# esp32_part_20190819.net
KiCad netlist of a schematic drawn in EAGLE
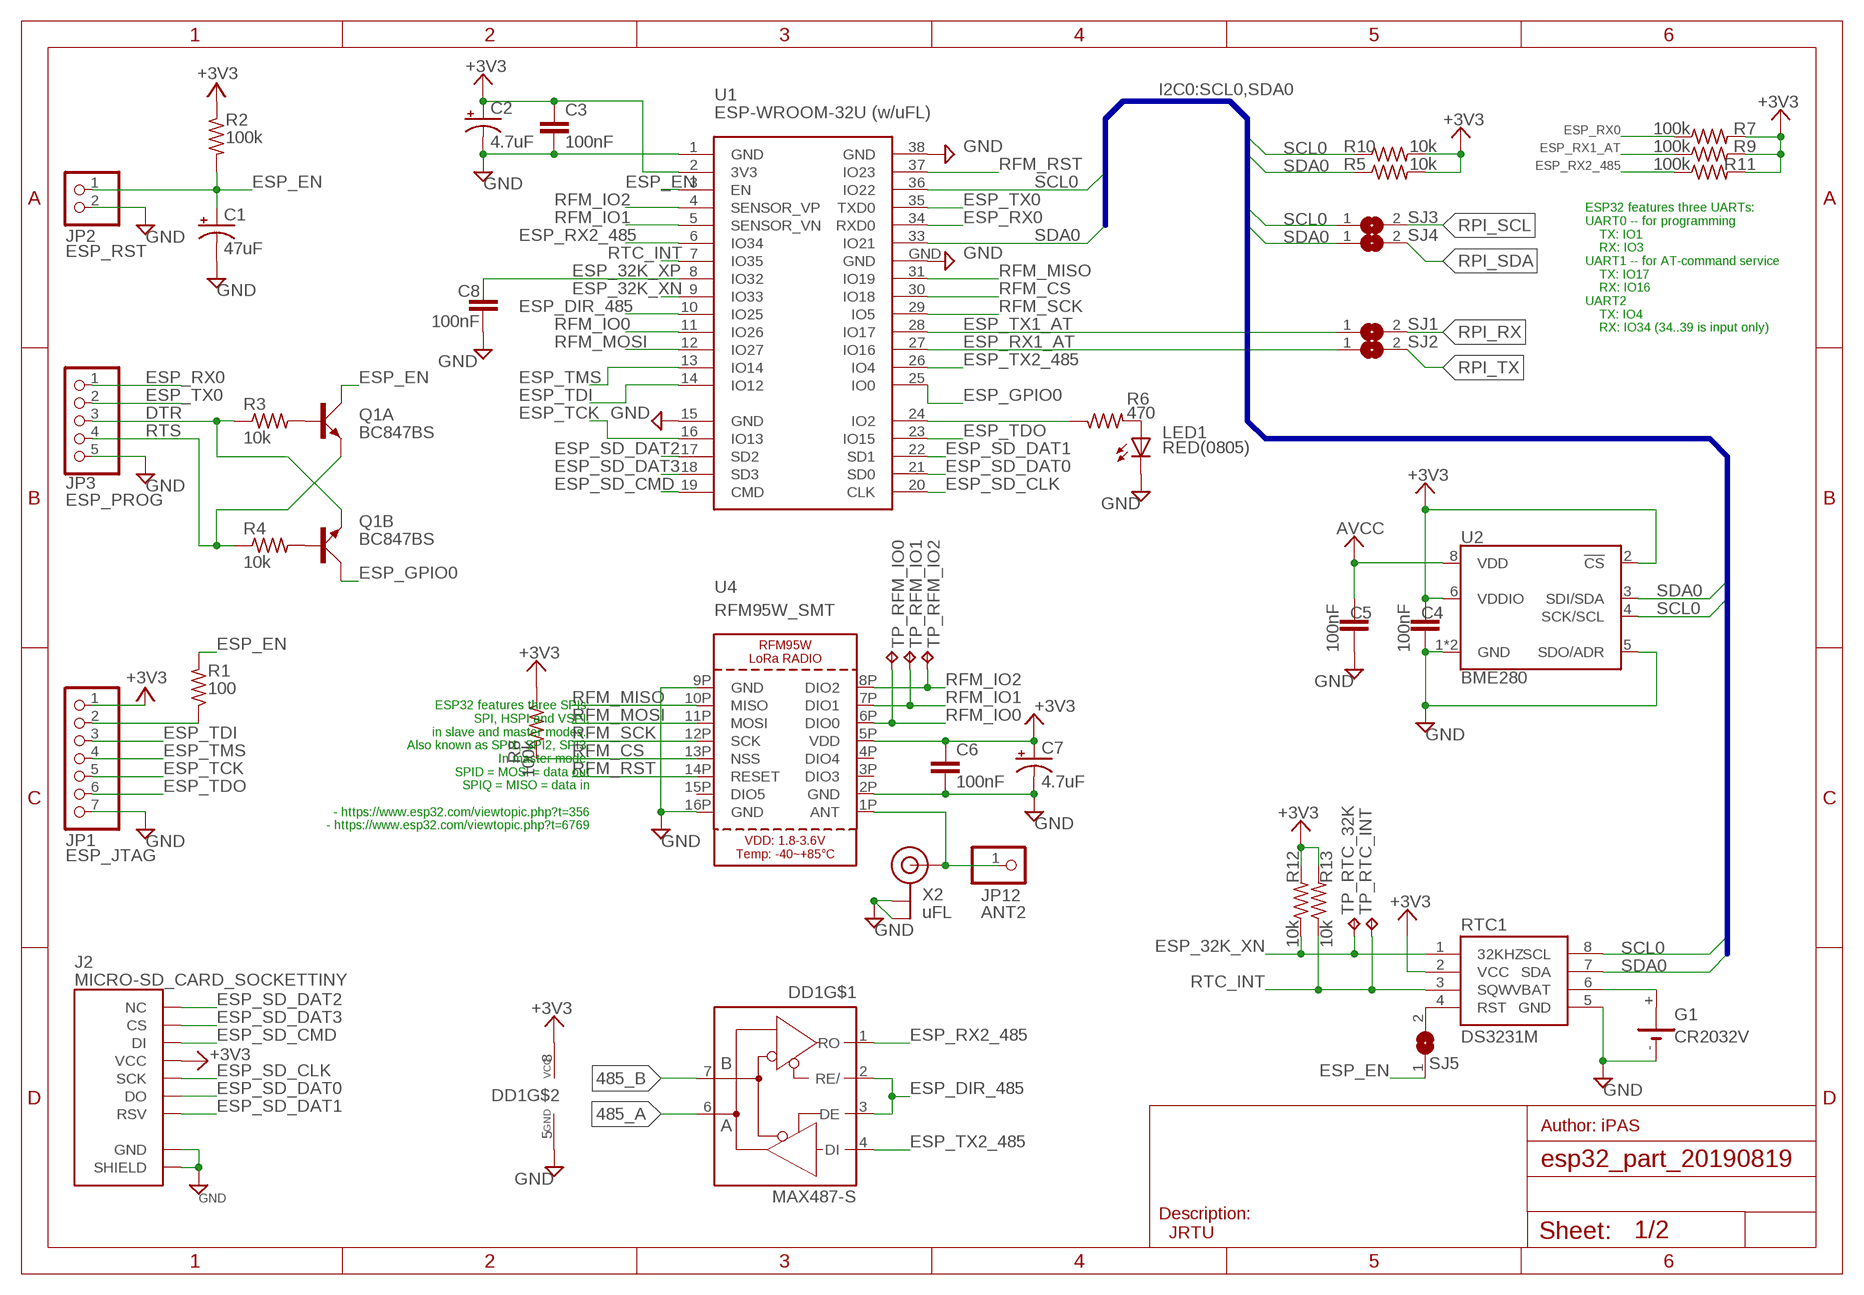
[diagram p0: schematic, sheet 1]
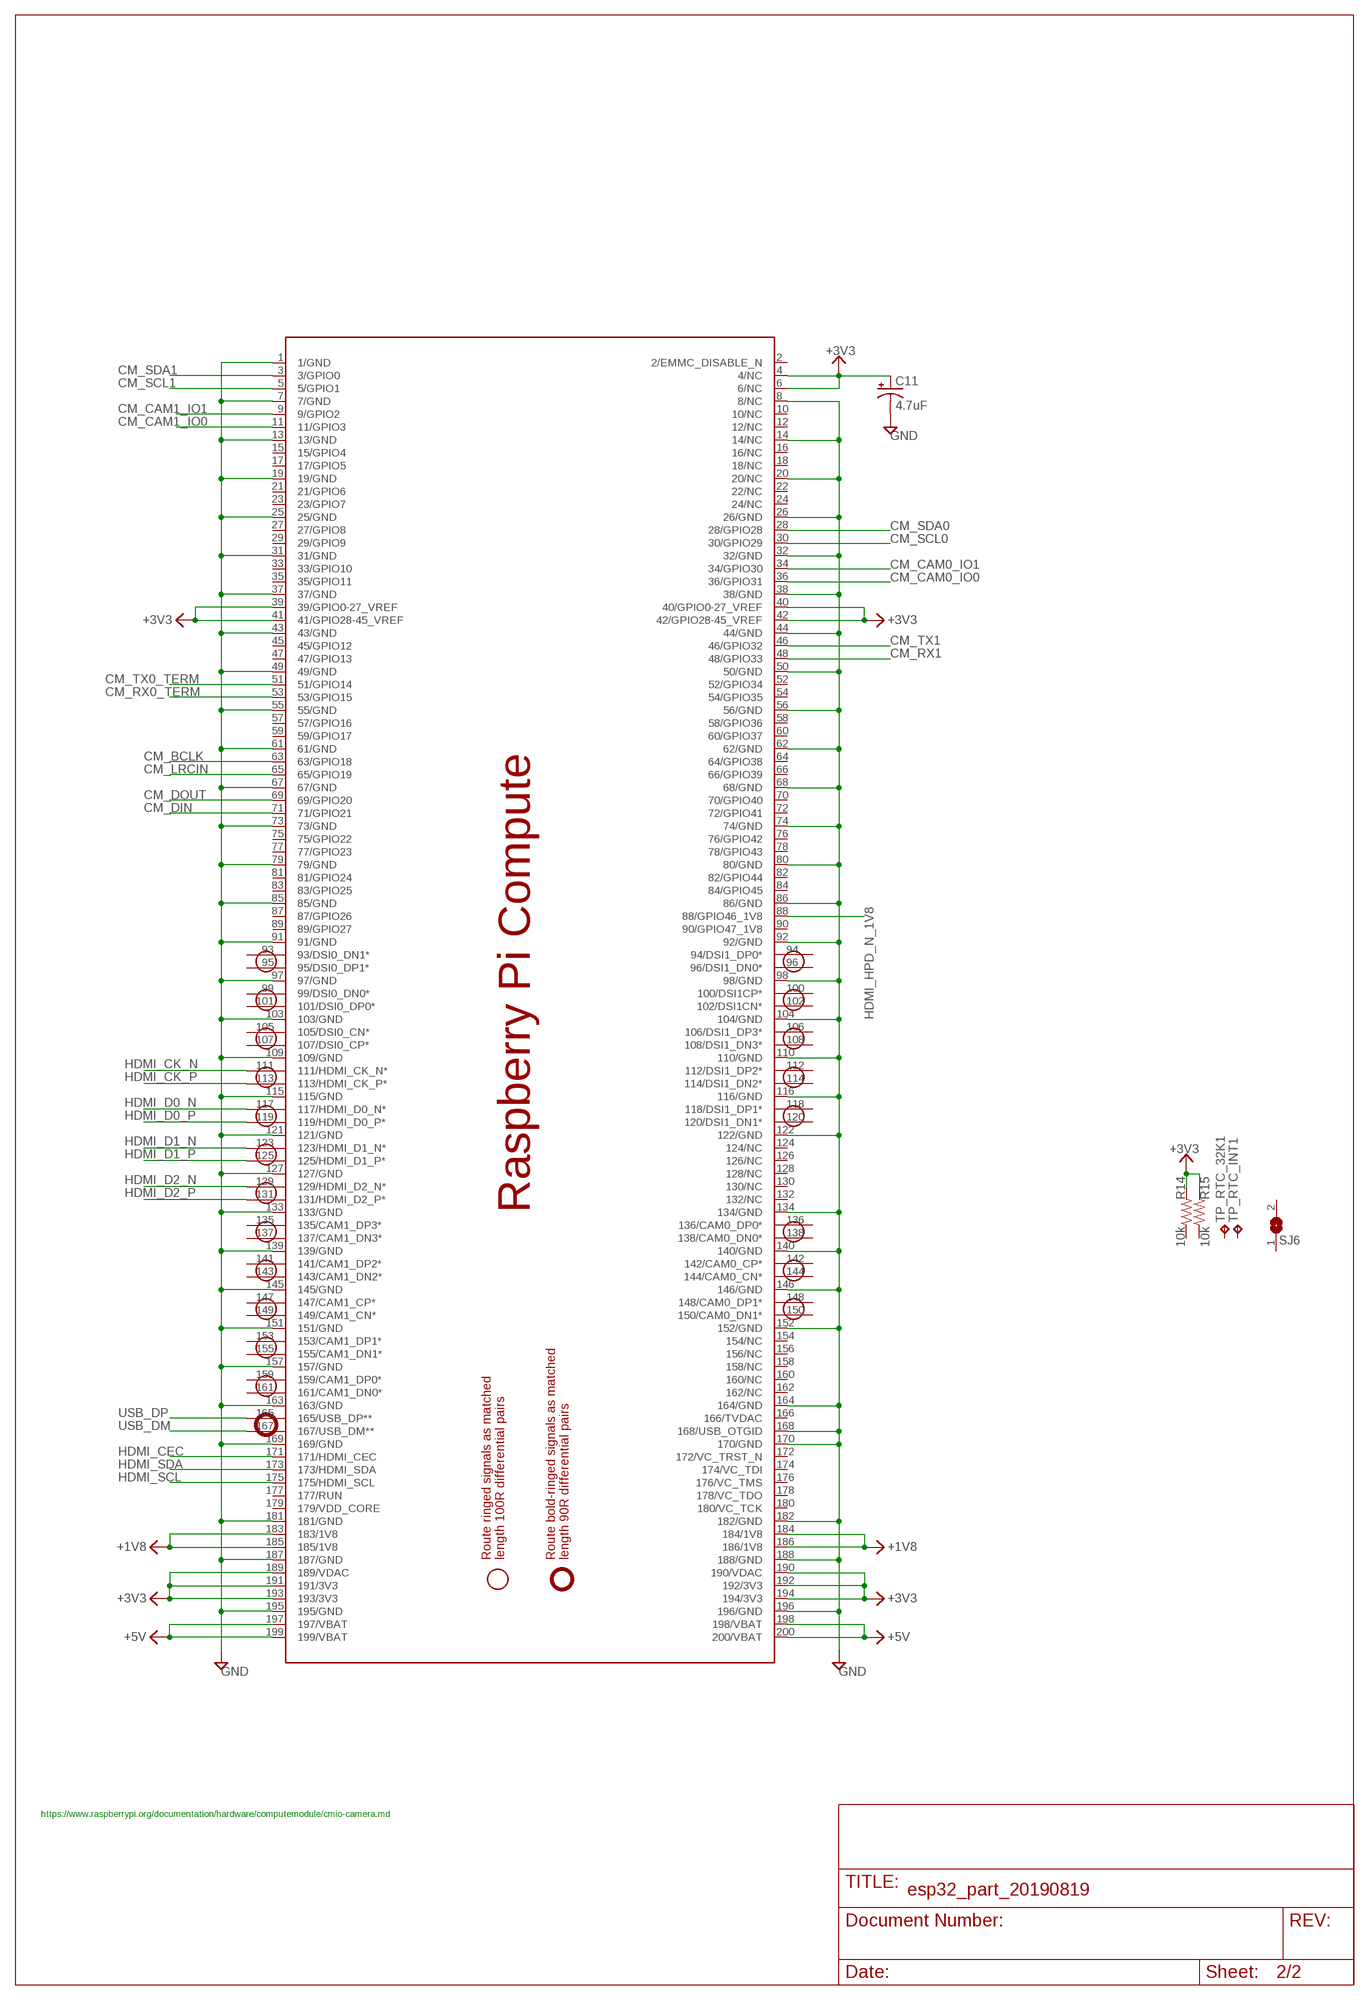
[diagram p1: schematic, sheet 2]

(export (version "E")
  (design (tool "Eeschema 10.0.6"))
  (components
    (comp (ref "C11")
      (value "4.7uF")
      (footprint "eagle-import:RCL_150CLZ-1014")
      (libsource (lib "eagle-import") (part "RCL_CPOL-US150CLZ-1014"))
    )
    (comp (ref "R14")
      (value "10k")
      (footprint "eagle-import:RCL_M0805")
      (libsource (lib "eagle-import") (part "RCL_R-USM0805"))
    )
    (comp (ref "R15")
      (value "10k")
      (footprint "eagle-import:RCL_M0805")
      (libsource (lib "eagle-import") (part "RCL_R-USM0805"))
    )
    (comp (ref "SJ6")
      (value "SOLDERJUMPERREFLOW")
      (footprint "eagle-import:SOLDERJUMPER_REFLOW")
      (libsource (lib "eagle-import") (part "SOLDERJUMPERREFLOW"))
    )
    (comp (ref "SODIMM")
      (value "RPI_COMPUTE")
      (footprint "eagle-import:RPI_COMPUTE")
      (libsource (lib "eagle-import") (part "RPI_COMPUTE"))
    )
    (comp (ref "TP_RTC_32K1")
      (value "TPB1,27")
      (footprint "eagle-import:B1,27")
      (libsource (lib "eagle-import") (part "TPB1,27"))
    )
    (comp (ref "TP_RTC_INT1")
      (value "TPB1,27")
      (footprint "eagle-import:B1,27")
      (libsource (lib "eagle-import") (part "TPB1,27"))
    )
    (comp (ref "C1")
      (value "47uF")
      (footprint "eagle-import:RCL_150CLZ-1014")
      (libsource (lib "eagle-import") (part "RCL_CPOL-US150CLZ-1014"))
    )
    (comp (ref "C2")
      (value "4.7uF")
      (footprint "eagle-import:RCL_150CLZ-1014")
      (libsource (lib "eagle-import") (part "RCL_CPOL-US150CLZ-1014"))
    )
    (comp (ref "C3")
      (value "100nF")
      (footprint "eagle-import:RCL_C1206")
      (libsource (lib "eagle-import") (part "RCL_C-EUC1206"))
    )
    (comp (ref "C4")
      (value "100nF")
      (footprint "eagle-import:RCL_C1206")
      (libsource (lib "eagle-import") (part "RCL_C-EUC1206"))
    )
    (comp (ref "C5")
      (value "100nF")
      (footprint "eagle-import:RCL_C1206")
      (libsource (lib "eagle-import") (part "RCL_C-EUC1206"))
    )
    (comp (ref "C6")
      (value "100nF")
      (footprint "eagle-import:RCL_C1206")
      (libsource (lib "eagle-import") (part "RCL_C-EUC1206"))
    )
    (comp (ref "C7")
      (value "4.7uF")
      (footprint "eagle-import:RCL_150CLZ-1014")
      (libsource (lib "eagle-import") (part "RCL_CPOL-US150CLZ-1014"))
    )
    (comp (ref "C8")
      (value "100nF")
      (footprint "eagle-import:RCL_C1206")
      (libsource (lib "eagle-import") (part "RCL_C-EUC1206"))
    )
    (comp (ref "DD1")
      (value "MAX487-S")
      (footprint "eagle-import:SO08")
      (libsource (lib "eagle-import") (part "MAX487-S"))
    )
    (comp (ref "G1")
      (value "CR2032V")
      (footprint "eagle-import:CR2032V")
      (libsource (lib "eagle-import") (part "CR2032V"))
    )
    (comp (ref "J2")
      (value "MICRO-SD_CARD_SOCKETTINY")
      (footprint "eagle-import:MICROSD_TINY")
      (libsource (lib "eagle-import") (part "MICRO-SD_CARD_SOCKETTINY"))
    )
    (comp (ref "JP1")
      (value "ESP_JTAG")
      (footprint "eagle-import:1X07")
      (libsource (lib "eagle-import") (part "PINHD-1X7"))
    )
    (comp (ref "JP2")
      (value "ESP_RST")
      (footprint "eagle-import:1X02")
      (libsource (lib "eagle-import") (part "PINHD-1X2"))
    )
    (comp (ref "JP3")
      (value "ESP_PROG")
      (footprint "eagle-import:1X05")
      (libsource (lib "eagle-import") (part "PINHD-1X5"))
    )
    (comp (ref "JP12")
      (value "ANT2")
      (footprint "eagle-import:1X01_ROUND")
      (libsource (lib "eagle-import") (part "HEADER-1X1ROUND"))
    )
    (comp (ref "LED1")
      (value "RED(0805)")
      (footprint "eagle-import:CHIP-LED0805")
      (libsource (lib "eagle-import") (part "LEDCHIP-LED0805"))
    )
    (comp (ref "Q1")
      (value "BC847BS")
      (footprint "eagle-import:SOT363_PHILIPS")
      (libsource (lib "eagle-import") (part "BC847BS"))
    )
    (comp (ref "R1")
      (value "100")
      (footprint "eagle-import:RCL_M0805")
      (libsource (lib "eagle-import") (part "RCL_R-USM0805"))
    )
    (comp (ref "R2")
      (value "100k")
      (footprint "eagle-import:RCL_M0805")
      (libsource (lib "eagle-import") (part "RCL_R-USM0805"))
    )
    (comp (ref "R3")
      (value "10k")
      (footprint "eagle-import:RCL_M0805")
      (libsource (lib "eagle-import") (part "RCL_R-USM0805"))
    )
    (comp (ref "R4")
      (value "10k")
      (footprint "eagle-import:RCL_M0805")
      (libsource (lib "eagle-import") (part "RCL_R-USM0805"))
    )
    (comp (ref "R5")
      (value "10k")
      (footprint "eagle-import:RCL_M0805")
      (libsource (lib "eagle-import") (part "RCL_R-USM0805"))
    )
    (comp (ref "R6")
      (value "470")
      (footprint "eagle-import:RCL_M0805")
      (libsource (lib "eagle-import") (part "RCL_R-USM0805"))
    )
    (comp (ref "R7")
      (value "100k")
      (footprint "eagle-import:RCL_M0805")
      (libsource (lib "eagle-import") (part "RCL_R-USM0805"))
    )
    (comp (ref "R8")
      (value "100k")
      (footprint "eagle-import:RCL_M0805")
      (libsource (lib "eagle-import") (part "RCL_R-USM0805"))
    )
    (comp (ref "R9")
      (value "100k")
      (footprint "eagle-import:RCL_M0805")
      (libsource (lib "eagle-import") (part "RCL_R-USM0805"))
    )
    (comp (ref "R10")
      (value "10k")
      (footprint "eagle-import:RCL_M0805")
      (libsource (lib "eagle-import") (part "RCL_R-USM0805"))
    )
    (comp (ref "R11")
      (value "100k")
      (footprint "eagle-import:RCL_M0805")
      (libsource (lib "eagle-import") (part "RCL_R-USM0805"))
    )
    (comp (ref "R12")
      (value "10k")
      (footprint "eagle-import:RCL_M0805")
      (libsource (lib "eagle-import") (part "RCL_R-USM0805"))
    )
    (comp (ref "R13")
      (value "10k")
      (footprint "eagle-import:RCL_M0805")
      (libsource (lib "eagle-import") (part "RCL_R-USM0805"))
    )
    (comp (ref "RTC1")
      (value "DS3231M")
      (footprint "eagle-import:SO08")
      (libsource (lib "eagle-import") (part "DS3231M"))
    )
    (comp (ref "SJ1")
      (value "SOLDERJUMPERREFLOW")
      (footprint "eagle-import:SOLDERJUMPER_REFLOW")
      (libsource (lib "eagle-import") (part "SOLDERJUMPERREFLOW"))
    )
    (comp (ref "SJ2")
      (value "SOLDERJUMPERREFLOW")
      (footprint "eagle-import:SOLDERJUMPER_REFLOW")
      (libsource (lib "eagle-import") (part "SOLDERJUMPERREFLOW"))
    )
    (comp (ref "SJ3")
      (value "SOLDERJUMPERREFLOW")
      (footprint "eagle-import:SOLDERJUMPER_REFLOW")
      (libsource (lib "eagle-import") (part "SOLDERJUMPERREFLOW"))
    )
    (comp (ref "SJ4")
      (value "SOLDERJUMPERREFLOW")
      (footprint "eagle-import:SOLDERJUMPER_REFLOW")
      (libsource (lib "eagle-import") (part "SOLDERJUMPERREFLOW"))
    )
    (comp (ref "SJ5")
      (value "SOLDERJUMPERREFLOW")
      (footprint "eagle-import:SOLDERJUMPER_REFLOW")
      (libsource (lib "eagle-import") (part "SOLDERJUMPERREFLOW"))
    )
    (comp (ref "TP_RFM_IO0")
      (value "TPB1,27")
      (footprint "eagle-import:B1,27")
      (libsource (lib "eagle-import") (part "TPB1,27"))
    )
    (comp (ref "TP_RFM_IO1")
      (value "TPB1,27")
      (footprint "eagle-import:B1,27")
      (libsource (lib "eagle-import") (part "TPB1,27"))
    )
    (comp (ref "TP_RFM_IO2")
      (value "TPB1,27")
      (footprint "eagle-import:B1,27")
      (libsource (lib "eagle-import") (part "TPB1,27"))
    )
    (comp (ref "TP_RTC_32K")
      (value "TPB1,27")
      (footprint "eagle-import:B1,27")
      (libsource (lib "eagle-import") (part "TPB1,27"))
    )
    (comp (ref "TP_RTC_INT")
      (value "TPB1,27")
      (footprint "eagle-import:B1,27")
      (libsource (lib "eagle-import") (part "TPB1,27"))
    )
    (comp (ref "U1")
      (value "ESP-WROOM-32U (w/uFL)")
      (footprint "eagle-import:ESP-WROOM-32")
      (libsource (lib "eagle-import") (part "ESP-WROOM-32"))
    )
    (comp (ref "U2")
      (value "BME280")
      (footprint "eagle-import:LGA-8-2.5X2.5")
      (libsource (lib "eagle-import") (part "BME280"))
    )
    (comp (ref "U4")
      (value "RFM95W_SMT")
      (footprint "eagle-import:RFMHCW_SMT")
      (libsource (lib "eagle-import") (part "RFM95W_SMT"))
    )
    (comp (ref "X2")
      (value "uFL")
      (footprint "eagle-import:U.FL")
      (libsource (lib "eagle-import") (part "ANTENNA_U.FL"))
    )
  )
  (nets
    (net (code "2") (name "+3V3") (class "Default")
      (node (ref "C11") (pin "+") (pinfunction "+_+") (pintype "passive"))
      (node (ref "C2") (pin "+") (pinfunction "+_+") (pintype "passive"))
      (node (ref "C3") (pin "1") (pinfunction "1_1") (pintype "passive"))
      (node (ref "C4") (pin "1") (pinfunction "1_1") (pintype "passive"))
      (node (ref "C6") (pin "1") (pinfunction "1_1") (pintype "passive"))
      (node (ref "C7") (pin "+") (pinfunction "+_+") (pintype "passive"))
      (node (ref "DD1") (pin "8") (pinfunction "VCC_8") (pintype "power_in"))
      (node (ref "J2") (pin "4") (pinfunction "VCC_4") (pintype "bidirectional"))
      (node (ref "JP1") (pin "1") (pinfunction "1_1") (pintype "passive"))
      (node (ref "R10") (pin "2") (pinfunction "2_2") (pintype "passive"))
      (node (ref "R11") (pin "2") (pinfunction "2_2") (pintype "passive"))
      (node (ref "R12") (pin "2") (pinfunction "2_2") (pintype "passive"))
      (node (ref "R13") (pin "2") (pinfunction "2_2") (pintype "passive"))
      (node (ref "R14") (pin "2") (pinfunction "2_2") (pintype "passive"))
      (node (ref "R15") (pin "2") (pinfunction "2_2") (pintype "passive"))
      (node (ref "R2") (pin "1") (pinfunction "1_1") (pintype "passive"))
      (node (ref "R5") (pin "2") (pinfunction "2_2") (pintype "passive"))
      (node (ref "R7") (pin "2") (pinfunction "2_2") (pintype "passive"))
      (node (ref "R8") (pin "1") (pinfunction "1_1") (pintype "passive"))
      (node (ref "R9") (pin "2") (pinfunction "2_2") (pintype "passive"))
      (node (ref "RTC1") (pin "2") (pinfunction "VCC_2") (pintype "power_in"))
      (node (ref "SODIMM") (pin "183") (pinfunction "183/1V8_183") (pintype "bidirectional"))
      (node (ref "SODIMM") (pin "184") (pinfunction "184/1V8_184") (pintype "bidirectional"))
      (node (ref "SODIMM") (pin "185") (pinfunction "185/1V8_185") (pintype "bidirectional"))
      (node (ref "SODIMM") (pin "186") (pinfunction "186/1V8_186") (pintype "bidirectional"))
      (node (ref "SODIMM") (pin "189") (pinfunction "189/VDAC_189") (pintype "bidirectional"))
      (node (ref "SODIMM") (pin "190") (pinfunction "190/VDAC_190") (pintype "bidirectional"))
      (node (ref "SODIMM") (pin "191") (pinfunction "191/3V3_191") (pintype "bidirectional"))
      (node (ref "SODIMM") (pin "192") (pinfunction "192/3V3_192") (pintype "bidirectional"))
      (node (ref "SODIMM") (pin "193") (pinfunction "193/3V3_193") (pintype "bidirectional"))
      (node (ref "SODIMM") (pin "194") (pinfunction "194/3V3_194") (pintype "bidirectional"))
      (node (ref "SODIMM") (pin "39") (pinfunction "39/GPIO0-27_VREF_39") (pintype "bidirectional"))
      (node (ref "SODIMM") (pin "4") (pinfunction "4/NC_4") (pintype "bidirectional"))
      (node (ref "SODIMM") (pin "40") (pinfunction "40/GPIO0-27_VREF_40") (pintype "bidirectional"))
      (node (ref "SODIMM") (pin "41") (pinfunction "41/GPIO28-45_VREF_41") (pintype "bidirectional"))
      (node (ref "SODIMM") (pin "42") (pinfunction "42/GPIO28-45_VREF_42") (pintype "bidirectional"))
      (node (ref "SODIMM") (pin "6") (pinfunction "6/NC_6") (pintype "bidirectional"))
      (node (ref "U1") (pin "2") (pinfunction "3V3_2") (pintype "power_in"))
      (node (ref "U2") (pin "2") (pinfunction "~{CS}_2") (pintype "bidirectional"))
      (node (ref "U2") (pin "6") (pinfunction "VDDIO_6") (pintype "bidirectional"))
      (node (ref "U4") (pin "5P") (pinfunction "VDD_5P") (pintype "power_in"))
    )
    (net (code "3") (name "+5V") (class "Default")
      (node (ref "SODIMM") (pin "197") (pinfunction "197/VBAT_197") (pintype "bidirectional"))
      (node (ref "SODIMM") (pin "198") (pinfunction "198/VBAT_198") (pintype "bidirectional"))
      (node (ref "SODIMM") (pin "199") (pinfunction "199/VBAT_199") (pintype "bidirectional"))
      (node (ref "SODIMM") (pin "200") (pinfunction "200/VBAT_200") (pintype "bidirectional"))
    )
    (net (code "5") (name "485_A") (class "Default")
      (node (ref "DD1") (pin "6") (pinfunction "A_6") (pintype "passive"))
    )
    (net (code "6") (name "485_B") (class "Default")
      (node (ref "DD1") (pin "7") (pinfunction "B_7") (pintype "passive"))
    )
    (net (code "7") (name "AVCC") (class "Default")
      (node (ref "C5") (pin "1") (pinfunction "1_1") (pintype "passive"))
      (node (ref "U2") (pin "8") (pinfunction "VDD_8") (pintype "bidirectional"))
    )
    (net (code "8") (name "CM_BCLK") (class "Default")
      (node (ref "SODIMM") (pin "63") (pinfunction "63/GPIO18_63") (pintype "bidirectional"))
    )
    (net (code "9") (name "CM_CAM0_IO0") (class "Default")
      (node (ref "SODIMM") (pin "36") (pinfunction "36/GPIO31_36") (pintype "bidirectional"))
    )
    (net (code "10") (name "CM_CAM0_IO1") (class "Default")
      (node (ref "SODIMM") (pin "34") (pinfunction "34/GPIO30_34") (pintype "bidirectional"))
    )
    (net (code "11") (name "CM_CAM1_IO0") (class "Default")
      (node (ref "SODIMM") (pin "11") (pinfunction "11/GPIO3_11") (pintype "bidirectional"))
    )
    (net (code "12") (name "CM_CAM1_IO1") (class "Default")
      (node (ref "SODIMM") (pin "9") (pinfunction "9/GPIO2_9") (pintype "bidirectional"))
    )
    (net (code "13") (name "CM_DIN") (class "Default")
      (node (ref "SODIMM") (pin "71") (pinfunction "71/GPIO21_71") (pintype "bidirectional"))
    )
    (net (code "14") (name "CM_DOUT") (class "Default")
      (node (ref "SODIMM") (pin "69") (pinfunction "69/GPIO20_69") (pintype "bidirectional"))
    )
    (net (code "15") (name "CM_LRCIN") (class "Default")
      (node (ref "SODIMM") (pin "65") (pinfunction "65/GPIO19_65") (pintype "bidirectional"))
    )
    (net (code "16") (name "CM_RX0_TERM") (class "Default")
      (node (ref "SODIMM") (pin "53") (pinfunction "53/GPIO15_53") (pintype "bidirectional"))
    )
    (net (code "17") (name "CM_RX1") (class "Default")
      (node (ref "SODIMM") (pin "48") (pinfunction "48/GPIO33_48") (pintype "bidirectional"))
    )
    (net (code "18") (name "CM_SCL0") (class "Default")
      (node (ref "SODIMM") (pin "30") (pinfunction "30/GPIO29_30") (pintype "bidirectional"))
    )
    (net (code "19") (name "CM_SCL1") (class "Default")
      (node (ref "SODIMM") (pin "5") (pinfunction "5/GPIO1_5") (pintype "bidirectional"))
    )
    (net (code "20") (name "CM_SDA0") (class "Default")
      (node (ref "SODIMM") (pin "28") (pinfunction "28/GPIO28_28") (pintype "bidirectional"))
    )
    (net (code "21") (name "CM_SDA1") (class "Default")
      (node (ref "SODIMM") (pin "3") (pinfunction "3/GPIO0_3") (pintype "bidirectional"))
    )
    (net (code "22") (name "CM_TX0_TERM") (class "Default")
      (node (ref "SODIMM") (pin "51") (pinfunction "51/GPIO14_51") (pintype "bidirectional"))
    )
    (net (code "23") (name "CM_TX1") (class "Default")
      (node (ref "SODIMM") (pin "46") (pinfunction "46/GPIO32_46") (pintype "bidirectional"))
    )
    (net (code "24") (name "DTR") (class "Default")
      (node (ref "JP3") (pin "3") (pinfunction "3_3") (pintype "passive"))
      (node (ref "Q1") (pin "4") (pinfunction "E_4") (pintype "passive"))
      (node (ref "R3") (pin "1") (pinfunction "1_1") (pintype "passive"))
    )
    (net (code "25") (name "ESP_32K_XN") (class "Default")
      (node (ref "R12") (pin "1") (pinfunction "1_1") (pintype "passive"))
      (node (ref "RTC1") (pin "1") (pinfunction "32KHZ_1") (pintype "output"))
      (node (ref "TP_RTC_32K") (pin "TP") (pinfunction "TP_TP") (pintype "input"))
      (node (ref "U1") (pin "9") (pinfunction "IO33_9") (pintype "bidirectional"))
    )
    (net (code "26") (name "ESP_32K_XP") (class "Default")
      (node (ref "C8") (pin "2") (pinfunction "2_2") (pintype "passive"))
      (node (ref "U1") (pin "8") (pinfunction "IO32_8") (pintype "bidirectional"))
    )
    (net (code "27") (name "ESP_DIR_485") (class "Default")
      (node (ref "DD1") (pin "2") (pinfunction "RE/_2") (pintype "input"))
      (node (ref "DD1") (pin "3") (pinfunction "DE_3") (pintype "input"))
      (node (ref "U1") (pin "10") (pinfunction "IO25_10") (pintype "bidirectional"))
    )
    (net (code "28") (name "ESP_EN") (class "Default")
      (node (ref "C1") (pin "+") (pinfunction "+_+") (pintype "passive"))
      (node (ref "JP2") (pin "1") (pinfunction "1_1") (pintype "passive"))
      (node (ref "Q1") (pin "6") (pinfunction "C_6") (pintype "passive"))
      (node (ref "R1") (pin "2") (pinfunction "2_2") (pintype "passive"))
      (node (ref "R2") (pin "2") (pinfunction "2_2") (pintype "passive"))
      (node (ref "SJ5") (pin "1") (pinfunction "1_1") (pintype "passive"))
      (node (ref "U1") (pin "3") (pinfunction "EN_3") (pintype "input"))
    )
    (net (code "29") (name "ESP_GPIO0") (class "Default")
      (node (ref "Q1") (pin "3") (pinfunction "C_3") (pintype "passive"))
      (node (ref "U1") (pin "25") (pinfunction "IO0_25") (pintype "bidirectional"))
    )
    (net (code "30") (name "ESP_RX0") (class "Default")
      (node (ref "JP3") (pin "1") (pinfunction "1_1") (pintype "passive"))
      (node (ref "R7") (pin "1") (pinfunction "1_1") (pintype "passive"))
      (node (ref "U1") (pin "34") (pinfunction "RXD0_34") (pintype "bidirectional"))
    )
    (net (code "31") (name "ESP_RX1_AT") (class "Default")
      (node (ref "R9") (pin "1") (pinfunction "1_1") (pintype "passive"))
      (node (ref "SJ2") (pin "1") (pinfunction "1_1") (pintype "passive"))
      (node (ref "U1") (pin "27") (pinfunction "IO16_27") (pintype "bidirectional"))
    )
    (net (code "32") (name "ESP_RX2_485") (class "Default")
      (node (ref "DD1") (pin "1") (pinfunction "RO_1") (pintype "output"))
      (node (ref "R11") (pin "1") (pinfunction "1_1") (pintype "passive"))
      (node (ref "U1") (pin "6") (pinfunction "IO34_6") (pintype "bidirectional"))
    )
    (net (code "33") (name "ESP_SD_CLK") (class "Default")
      (node (ref "J2") (pin "5") (pinfunction "SCK_5") (pintype "bidirectional"))
      (node (ref "U1") (pin "20") (pinfunction "CLK_20") (pintype "bidirectional"))
    )
    (net (code "34") (name "ESP_SD_CMD") (class "Default")
      (node (ref "J2") (pin "3") (pinfunction "DI_3") (pintype "bidirectional"))
      (node (ref "U1") (pin "19") (pinfunction "CMD_19") (pintype "bidirectional"))
    )
    (net (code "35") (name "ESP_SD_DAT0") (class "Default")
      (node (ref "J2") (pin "7") (pinfunction "DO_7") (pintype "bidirectional"))
      (node (ref "U1") (pin "21") (pinfunction "SD0_21") (pintype "bidirectional"))
    )
    (net (code "36") (name "ESP_SD_DAT1") (class "Default")
      (node (ref "J2") (pin "1") (pinfunction "RSV_1") (pintype "bidirectional"))
      (node (ref "J2") (pin "8") (pinfunction "RSV_8") (pintype "bidirectional"))
      (node (ref "U1") (pin "22") (pinfunction "SD1_22") (pintype "bidirectional"))
    )
    (net (code "37") (name "ESP_SD_DAT2") (class "Default")
      (node (ref "J2") (pin "9") (pinfunction "NC_9") (pintype "bidirectional"))
      (node (ref "U1") (pin "17") (pinfunction "SD2_17") (pintype "bidirectional"))
    )
    (net (code "38") (name "ESP_SD_DAT3") (class "Default")
      (node (ref "J2") (pin "2") (pinfunction "CS_2") (pintype "bidirectional"))
      (node (ref "U1") (pin "18") (pinfunction "SD3_18") (pintype "bidirectional"))
    )
    (net (code "39") (name "ESP_TCK") (class "Default")
      (node (ref "JP1") (pin "5") (pinfunction "5_5") (pintype "passive"))
      (node (ref "U1") (pin "16") (pinfunction "IO13_16") (pintype "bidirectional"))
    )
    (net (code "40") (name "ESP_TDI") (class "Default")
      (node (ref "JP1") (pin "3") (pinfunction "3_3") (pintype "passive"))
      (node (ref "U1") (pin "14") (pinfunction "IO12_14") (pintype "bidirectional"))
    )
    (net (code "41") (name "ESP_TDO") (class "Default")
      (node (ref "JP1") (pin "6") (pinfunction "6_6") (pintype "passive"))
      (node (ref "U1") (pin "23") (pinfunction "IO15_23") (pintype "bidirectional"))
    )
    (net (code "42") (name "ESP_TMS") (class "Default")
      (node (ref "JP1") (pin "4") (pinfunction "4_4") (pintype "passive"))
      (node (ref "U1") (pin "13") (pinfunction "IO14_13") (pintype "bidirectional"))
    )
    (net (code "43") (name "ESP_TX0") (class "Default")
      (node (ref "JP3") (pin "2") (pinfunction "2_2") (pintype "passive"))
      (node (ref "U1") (pin "35") (pinfunction "TXD0_35") (pintype "bidirectional"))
    )
    (net (code "44") (name "ESP_TX1_AT") (class "Default")
      (node (ref "SJ1") (pin "1") (pinfunction "1_1") (pintype "passive"))
      (node (ref "U1") (pin "28") (pinfunction "IO17_28") (pintype "bidirectional"))
    )
    (net (code "45") (name "ESP_TX2_485") (class "Default")
      (node (ref "DD1") (pin "4") (pinfunction "DI_4") (pintype "input"))
      (node (ref "U1") (pin "26") (pinfunction "IO4_26") (pintype "bidirectional"))
    )
    (net (code "46") (name "GND") (class "Default")
      (node (ref "C1") (pin "-") (pinfunction "-_-") (pintype "passive"))
      (node (ref "C11") (pin "-") (pinfunction "-_-") (pintype "passive"))
      (node (ref "C2") (pin "-") (pinfunction "-_-") (pintype "passive"))
      (node (ref "C3") (pin "2") (pinfunction "2_2") (pintype "passive"))
      (node (ref "C4") (pin "2") (pinfunction "2_2") (pintype "passive"))
      (node (ref "C5") (pin "2") (pinfunction "2_2") (pintype "passive"))
      (node (ref "C6") (pin "2") (pinfunction "2_2") (pintype "passive"))
      (node (ref "C7") (pin "-") (pinfunction "-_-") (pintype "passive"))
      (node (ref "C8") (pin "1") (pinfunction "1_1") (pintype "passive"))
      (node (ref "DD1") (pin "5") (pinfunction "GND_5") (pintype "power_in"))
      (node (ref "G1") (pin "-") (pinfunction "-_-") (pintype "passive"))
      (node (ref "J2") (pin "6") (pinfunction "GND_6") (pintype "bidirectional"))
      (node (ref "J2") (pin "GND1") (pinfunction "SHIELD_GND1") (pintype "bidirectional"))
      (node (ref "J2") (pin "GND2") (pinfunction "SHIELD_GND2") (pintype "bidirectional"))
      (node (ref "J2") (pin "GND3") (pinfunction "SHIELD_GND3") (pintype "bidirectional"))
      (node (ref "J2") (pin "GND4") (pinfunction "SHIELD_GND4") (pintype "bidirectional"))
      (node (ref "J2") (pin "GND5") (pinfunction "SHIELD_GND5") (pintype "bidirectional"))
      (node (ref "J2") (pin "GND6") (pinfunction "SHIELD_GND6") (pintype "bidirectional"))
      (node (ref "JP1") (pin "7") (pinfunction "7_7") (pintype "passive"))
      (node (ref "JP2") (pin "2") (pinfunction "2_2") (pintype "passive"))
      (node (ref "JP3") (pin "5") (pinfunction "5_5") (pintype "passive"))
      (node (ref "LED1") (pin "C") (pinfunction "C_C") (pintype "passive"))
      (node (ref "RTC1") (pin "5") (pinfunction "GND_5") (pintype "power_in"))
      (node (ref "SODIMM") (pin "1") (pinfunction "1/GND_1") (pintype "bidirectional"))
      (node (ref "SODIMM") (pin "103") (pinfunction "103/GND_103") (pintype "bidirectional"))
      (node (ref "SODIMM") (pin "104") (pinfunction "104/GND_104") (pintype "bidirectional"))
      (node (ref "SODIMM") (pin "109") (pinfunction "109/GND_109") (pintype "bidirectional"))
      (node (ref "SODIMM") (pin "110") (pinfunction "110/GND_110") (pintype "bidirectional"))
      (node (ref "SODIMM") (pin "115") (pinfunction "115/GND_115") (pintype "bidirectional"))
      (node (ref "SODIMM") (pin "116") (pinfunction "116/GND_116") (pintype "bidirectional"))
      (node (ref "SODIMM") (pin "121") (pinfunction "121/GND_121") (pintype "bidirectional"))
      (node (ref "SODIMM") (pin "122") (pinfunction "122/GND_122") (pintype "bidirectional"))
      (node (ref "SODIMM") (pin "127") (pinfunction "127/GND_127") (pintype "bidirectional"))
      (node (ref "SODIMM") (pin "13") (pinfunction "13/GND_13") (pintype "bidirectional"))
      (node (ref "SODIMM") (pin "133") (pinfunction "133/GND_133") (pintype "bidirectional"))
      (node (ref "SODIMM") (pin "134") (pinfunction "134/GND_134") (pintype "bidirectional"))
      (node (ref "SODIMM") (pin "139") (pinfunction "139/GND_139") (pintype "bidirectional"))
      (node (ref "SODIMM") (pin "14") (pinfunction "14/NC_14") (pintype "bidirectional"))
      (node (ref "SODIMM") (pin "140") (pinfunction "140/GND_140") (pintype "bidirectional"))
      (node (ref "SODIMM") (pin "145") (pinfunction "145/GND_145") (pintype "bidirectional"))
      (node (ref "SODIMM") (pin "146") (pinfunction "146/GND_146") (pintype "bidirectional"))
      (node (ref "SODIMM") (pin "151") (pinfunction "151/GND_151") (pintype "bidirectional"))
      (node (ref "SODIMM") (pin "152") (pinfunction "152/GND_152") (pintype "bidirectional"))
      (node (ref "SODIMM") (pin "157") (pinfunction "157/GND_157") (pintype "bidirectional"))
      (node (ref "SODIMM") (pin "163") (pinfunction "163/GND_163") (pintype "bidirectional"))
      (node (ref "SODIMM") (pin "164") (pinfunction "164/GND_164") (pintype "bidirectional"))
      (node (ref "SODIMM") (pin "168") (pinfunction "168/USB_OTGID_168") (pintype "bidirectional"))
      (node (ref "SODIMM") (pin "169") (pinfunction "169/GND_169") (pintype "bidirectional"))
      (node (ref "SODIMM") (pin "170") (pinfunction "170/GND_170") (pintype "bidirectional"))
      (node (ref "SODIMM") (pin "181") (pinfunction "181/GND_181") (pintype "bidirectional"))
      (node (ref "SODIMM") (pin "182") (pinfunction "182/GND_182") (pintype "bidirectional"))
      (node (ref "SODIMM") (pin "187") (pinfunction "187/GND_187") (pintype "bidirectional"))
      (node (ref "SODIMM") (pin "188") (pinfunction "188/GND_188") (pintype "bidirectional"))
      (node (ref "SODIMM") (pin "19") (pinfunction "19/GND_19") (pintype "bidirectional"))
      (node (ref "SODIMM") (pin "195") (pinfunction "195/GND_195") (pintype "bidirectional"))
      (node (ref "SODIMM") (pin "196") (pinfunction "196/GND_196") (pintype "bidirectional"))
      (node (ref "SODIMM") (pin "20") (pinfunction "20/NC_20") (pintype "bidirectional"))
      (node (ref "SODIMM") (pin "25") (pinfunction "25/GND_25") (pintype "bidirectional"))
      (node (ref "SODIMM") (pin "26") (pinfunction "26/GND_26") (pintype "bidirectional"))
      (node (ref "SODIMM") (pin "31") (pinfunction "31/GND_31") (pintype "bidirectional"))
      (node (ref "SODIMM") (pin "32") (pinfunction "32/GND_32") (pintype "bidirectional"))
      (node (ref "SODIMM") (pin "37") (pinfunction "37/GND_37") (pintype "bidirectional"))
      (node (ref "SODIMM") (pin "38") (pinfunction "38/GND_38") (pintype "bidirectional"))
      (node (ref "SODIMM") (pin "43") (pinfunction "43/GND_43") (pintype "bidirectional"))
      (node (ref "SODIMM") (pin "44") (pinfunction "44/GND_44") (pintype "bidirectional"))
      (node (ref "SODIMM") (pin "49") (pinfunction "49/GND_49") (pintype "bidirectional"))
      (node (ref "SODIMM") (pin "50") (pinfunction "50/GND_50") (pintype "bidirectional"))
      (node (ref "SODIMM") (pin "55") (pinfunction "55/GND_55") (pintype "bidirectional"))
      (node (ref "SODIMM") (pin "56") (pinfunction "56/GND_56") (pintype "bidirectional"))
      (node (ref "SODIMM") (pin "61") (pinfunction "61/GND_61") (pintype "bidirectional"))
      (node (ref "SODIMM") (pin "62") (pinfunction "62/GND_62") (pintype "bidirectional"))
      (node (ref "SODIMM") (pin "67") (pinfunction "67/GND_67") (pintype "bidirectional"))
      (node (ref "SODIMM") (pin "68") (pinfunction "68/GND_68") (pintype "bidirectional"))
      (node (ref "SODIMM") (pin "7") (pinfunction "7/GND_7") (pintype "bidirectional"))
      (node (ref "SODIMM") (pin "73") (pinfunction "73/GND_73") (pintype "bidirectional"))
      (node (ref "SODIMM") (pin "74") (pinfunction "74/GND_74") (pintype "bidirectional"))
      (node (ref "SODIMM") (pin "79") (pinfunction "79/GND_79") (pintype "bidirectional"))
      (node (ref "SODIMM") (pin "8") (pinfunction "8/NC_8") (pintype "bidirectional"))
      (node (ref "SODIMM") (pin "80") (pinfunction "80/GND_80") (pintype "bidirectional"))
      (node (ref "SODIMM") (pin "85") (pinfunction "85/GND_85") (pintype "bidirectional"))
      (node (ref "SODIMM") (pin "86") (pinfunction "86/GND_86") (pintype "bidirectional"))
      (node (ref "SODIMM") (pin "91") (pinfunction "91/GND_91") (pintype "bidirectional"))
      (node (ref "SODIMM") (pin "92") (pinfunction "92/GND_92") (pintype "bidirectional"))
      (node (ref "SODIMM") (pin "97") (pinfunction "97/GND_97") (pintype "bidirectional"))
      (node (ref "SODIMM") (pin "98") (pinfunction "98/GND_98") (pintype "bidirectional"))
      (node (ref "U1") (pin "1") (pinfunction "GND_1") (pintype "power_in"))
      (node (ref "U1") (pin "15") (pinfunction "GND_15") (pintype "power_in"))
      (node (ref "U1") (pin "38") (pinfunction "GND_38") (pintype "power_in"))
      (node (ref "U1") (pin "GND") (pinfunction "GND_GND") (pintype "power_in"))
      (node (ref "U2") (pin "1") (pinfunction "GND_1") (pintype "bidirectional"))
      (node (ref "U2") (pin "5") (pinfunction "SDO/ADR_5") (pintype "bidirectional"))
      (node (ref "U2") (pin "7") (pinfunction "GND_7") (pintype "bidirectional"))
      (node (ref "U4") (pin "16P") (pinfunction "GND_16P") (pintype "power_in"))
      (node (ref "U4") (pin "2P") (pinfunction "GND_2P") (pintype "power_in"))
      (node (ref "U4") (pin "9P") (pinfunction "GND_9P") (pintype "power_in"))
      (node (ref "X2") (pin "1") (pinfunction "GND_1") (pintype "passive"))
      (node (ref "X2") (pin "2") (pinfunction "GND_2") (pintype "passive"))
    )
    (net (code "47") (name "HDMI_CEC") (class "Default")
      (node (ref "SODIMM") (pin "171") (pinfunction "171/HDMI_CEC_171") (pintype "bidirectional"))
    )
    (net (code "48") (name "HDMI_CK_N") (class "Default")
      (node (ref "SODIMM") (pin "111") (pinfunction "111/HDMI_CK_N*_111") (pintype "bidirectional"))
    )
    (net (code "49") (name "HDMI_CK_P") (class "Default")
      (node (ref "SODIMM") (pin "113") (pinfunction "113/HDMI_CK_P*_113") (pintype "bidirectional"))
    )
    (net (code "50") (name "HDMI_D0_N") (class "Default")
      (node (ref "SODIMM") (pin "117") (pinfunction "117/HDMI_D0_N*_117") (pintype "bidirectional"))
    )
    (net (code "51") (name "HDMI_D0_P") (class "Default")
      (node (ref "SODIMM") (pin "119") (pinfunction "119/HDMI_D0_P*_119") (pintype "bidirectional"))
    )
    (net (code "52") (name "HDMI_D1_N") (class "Default")
      (node (ref "SODIMM") (pin "123") (pinfunction "123/HDMI_D1_N*_123") (pintype "bidirectional"))
    )
    (net (code "53") (name "HDMI_D1_P") (class "Default")
      (node (ref "SODIMM") (pin "125") (pinfunction "125/HDMI_D1_P*_125") (pintype "bidirectional"))
    )
    (net (code "54") (name "HDMI_D2_N") (class "Default")
      (node (ref "SODIMM") (pin "129") (pinfunction "129/HDMI_D2_N*_129") (pintype "bidirectional"))
    )
    (net (code "55") (name "HDMI_D2_P") (class "Default")
      (node (ref "SODIMM") (pin "131") (pinfunction "131/HDMI_D2_P*_131") (pintype "bidirectional"))
    )
    (net (code "56") (name "HDMI_HPD_N_1V8") (class "Default")
      (node (ref "SODIMM") (pin "88") (pinfunction "88/GPIO46_1V8_88") (pintype "bidirectional"))
    )
    (net (code "57") (name "HDMI_SCL") (class "Default")
      (node (ref "SODIMM") (pin "175") (pinfunction "175/HDMI_SCL_175") (pintype "bidirectional"))
    )
    (net (code "58") (name "HDMI_SDA") (class "Default")
      (node (ref "SODIMM") (pin "173") (pinfunction "173/HDMI_SDA_173") (pintype "bidirectional"))
    )
    (net (code "59") (name "Net-(JP1-Pad2)") (class "Default")
      (node (ref "JP1") (pin "2") (pinfunction "2_2") (pintype "passive"))
      (node (ref "R1") (pin "1") (pinfunction "1_1") (pintype "passive"))
    )
    (net (code "60") (name "Net-(LED1-PadA)") (class "Default")
      (node (ref "LED1") (pin "A") (pinfunction "A_A") (pintype "passive"))
      (node (ref "R6") (pin "2") (pinfunction "2_2") (pintype "passive"))
    )
    (net (code "61") (name "Net-(Q1A-B)") (class "Default")
      (node (ref "Q1") (pin "2") (pinfunction "B_2") (pintype "passive"))
      (node (ref "R3") (pin "2") (pinfunction "2_2") (pintype "passive"))
    )
    (net (code "62") (name "Net-(Q1B-B)") (class "Default")
      (node (ref "Q1") (pin "5") (pinfunction "B_5") (pintype "passive"))
      (node (ref "R4") (pin "2") (pinfunction "2_2") (pintype "passive"))
    )
    (net (code "63") (name "Net-(RTC1-RST)") (class "Default")
      (node (ref "RTC1") (pin "4") (pinfunction "RST_4") (pintype "bidirectional"))
      (node (ref "SJ5") (pin "2") (pinfunction "2_2") (pintype "passive"))
    )
    (net (code "64") (name "Net-(RTC1-VBAT)") (class "Default")
      (node (ref "G1") (pin "+") (pinfunction "+_+") (pintype "passive"))
      (node (ref "RTC1") (pin "6") (pinfunction "VBAT_6") (pintype "power_in"))
    )
    (net (code "65") (name "Net-(U1-IO2)") (class "Default")
      (node (ref "R6") (pin "1") (pinfunction "1_1") (pintype "passive"))
      (node (ref "U1") (pin "24") (pinfunction "IO2_24") (pintype "bidirectional"))
    )
    (net (code "66") (name "Net-(U4-ANT)") (class "Default")
      (node (ref "JP12") (pin "1") (pinfunction "1_1") (pintype "passive"))
      (node (ref "U4") (pin "1P") (pinfunction "ANT_1P") (pintype "bidirectional"))
      (node (ref "X2") (pin "3") (pinfunction "SIGNAL_3") (pintype "passive"))
    )
    (net (code "67") (name "RFM_CS") (class "Default")
      (node (ref "R8") (pin "2") (pinfunction "2_2") (pintype "passive"))
      (node (ref "U1") (pin "30") (pinfunction "IO18_30") (pintype "bidirectional"))
      (node (ref "U4") (pin "13P") (pinfunction "NSS_13P") (pintype "input"))
    )
    (net (code "68") (name "RFM_IO0") (class "Default")
      (node (ref "TP_RFM_IO0") (pin "TP") (pinfunction "TP_TP") (pintype "input"))
      (node (ref "U1") (pin "11") (pinfunction "IO26_11") (pintype "bidirectional"))
      (node (ref "U4") (pin "6P") (pinfunction "DIO0_6P") (pintype "bidirectional"))
    )
    (net (code "69") (name "RFM_IO1") (class "Default")
      (node (ref "TP_RFM_IO1") (pin "TP") (pinfunction "TP_TP") (pintype "input"))
      (node (ref "U1") (pin "5") (pinfunction "SENSOR_VN_5") (pintype "bidirectional"))
      (node (ref "U4") (pin "7P") (pinfunction "DIO1_7P") (pintype "bidirectional"))
    )
    (net (code "70") (name "RFM_IO2") (class "Default")
      (node (ref "TP_RFM_IO2") (pin "TP") (pinfunction "TP_TP") (pintype "input"))
      (node (ref "U1") (pin "4") (pinfunction "SENSOR_VP_4") (pintype "bidirectional"))
      (node (ref "U4") (pin "8P") (pinfunction "DIO2_8P") (pintype "bidirectional"))
    )
    (net (code "71") (name "RFM_MISO") (class "Default")
      (node (ref "U1") (pin "31") (pinfunction "IO19_31") (pintype "bidirectional"))
      (node (ref "U4") (pin "10P") (pinfunction "MISO_10P") (pintype "output"))
    )
    (net (code "72") (name "RFM_MOSI") (class "Default")
      (node (ref "U1") (pin "12") (pinfunction "IO27_12") (pintype "bidirectional"))
      (node (ref "U4") (pin "11P") (pinfunction "MOSI_11P") (pintype "input"))
    )
    (net (code "73") (name "RFM_RST") (class "Default")
      (node (ref "U1") (pin "37") (pinfunction "IO23_37") (pintype "bidirectional"))
      (node (ref "U4") (pin "14P") (pinfunction "RESET_14P") (pintype "input"))
    )
    (net (code "74") (name "RFM_SCK") (class "Default")
      (node (ref "U1") (pin "29") (pinfunction "IO5_29") (pintype "bidirectional"))
      (node (ref "U4") (pin "12P") (pinfunction "SCK_12P") (pintype "input"))
    )
    (net (code "75") (name "RPI_RX") (class "Default")
      (node (ref "SJ1") (pin "2") (pinfunction "2_2") (pintype "passive"))
    )
    (net (code "76") (name "RPI_SCL") (class "Default")
      (node (ref "SJ3") (pin "2") (pinfunction "2_2") (pintype "passive"))
    )
    (net (code "77") (name "RPI_SDA") (class "Default")
      (node (ref "SJ4") (pin "2") (pinfunction "2_2") (pintype "passive"))
    )
    (net (code "78") (name "RPI_TX") (class "Default")
      (node (ref "SJ2") (pin "2") (pinfunction "2_2") (pintype "passive"))
    )
    (net (code "79") (name "RTC_INT") (class "Default")
      (node (ref "R13") (pin "1") (pinfunction "1_1") (pintype "passive"))
      (node (ref "RTC1") (pin "3") (pinfunction "SQW_3") (pintype "output"))
      (node (ref "TP_RTC_INT") (pin "TP") (pinfunction "TP_TP") (pintype "input"))
      (node (ref "U1") (pin "7") (pinfunction "IO35_7") (pintype "bidirectional"))
    )
    (net (code "80") (name "RTS") (class "Default")
      (node (ref "JP3") (pin "4") (pinfunction "4_4") (pintype "passive"))
      (node (ref "Q1") (pin "1") (pinfunction "E_1") (pintype "passive"))
      (node (ref "R4") (pin "1") (pinfunction "1_1") (pintype "passive"))
    )
    (net (code "81") (name "SCL0") (class "Default")
      (node (ref "R10") (pin "1") (pinfunction "1_1") (pintype "passive"))
      (node (ref "RTC1") (pin "8") (pinfunction "SCL_8") (pintype "bidirectional"))
      (node (ref "SJ3") (pin "1") (pinfunction "1_1") (pintype "passive"))
      (node (ref "U1") (pin "36") (pinfunction "IO22_36") (pintype "bidirectional"))
      (node (ref "U2") (pin "4") (pinfunction "SCK/SCL_4") (pintype "bidirectional"))
    )
    (net (code "82") (name "SDA0") (class "Default")
      (node (ref "R5") (pin "1") (pinfunction "1_1") (pintype "passive"))
      (node (ref "RTC1") (pin "7") (pinfunction "SDA_7") (pintype "bidirectional"))
      (node (ref "SJ4") (pin "1") (pinfunction "1_1") (pintype "passive"))
      (node (ref "U1") (pin "33") (pinfunction "IO21_33") (pintype "bidirectional"))
      (node (ref "U2") (pin "3") (pinfunction "SDI/SDA_3") (pintype "bidirectional"))
    )
    (net (code "83") (name "USB_DM") (class "Default")
      (node (ref "SODIMM") (pin "167") (pinfunction "167/USB_DM**_167") (pintype "bidirectional"))
    )
    (net (code "84") (name "USB_DP") (class "Default")
      (node (ref "SODIMM") (pin "165") (pinfunction "165/USB_DP**_165") (pintype "bidirectional"))
    )
    (net (code "85") (name "unconnected-(G1-+-Pad+@1)") (class "Default")
      (node (ref "G1") (pin "+@1") (pinfunction "+_+@1") (pintype "passive"))
    )
    (net (code "86") (name "unconnected-(R14-Pad1)") (class "Default")
      (node (ref "R14") (pin "1") (pinfunction "1_1") (pintype "passive"))
    )
    (net (code "87") (name "unconnected-(R15-Pad1)") (class "Default")
      (node (ref "R15") (pin "1") (pinfunction "1_1") (pintype "passive"))
    )
    (net (code "88") (name "unconnected-(SJ6-Pad1)") (class "Default")
      (node (ref "SJ6") (pin "1") (pinfunction "1_1") (pintype "passive"))
    )
    (net (code "89") (name "unconnected-(SJ6-Pad2)") (class "Default")
      (node (ref "SJ6") (pin "2") (pinfunction "2_2") (pintype "passive"))
    )
    (net (code "90") (name "unconnected-(SODIMM-2{slash}EMMC_DISABLE_N-Pad2)") (class "Default")
      (node (ref "SODIMM") (pin "2") (pinfunction "2/EMMC_DISABLE_N_2") (pintype "bidirectional"))
    )
    (net (code "91") (name "unconnected-(SODIMM-10{slash}NC-Pad10)") (class "Default")
      (node (ref "SODIMM") (pin "10") (pinfunction "10/NC_10") (pintype "bidirectional"))
    )
    (net (code "92") (name "unconnected-(SODIMM-12{slash}NC-Pad12)") (class "Default")
      (node (ref "SODIMM") (pin "12") (pinfunction "12/NC_12") (pintype "bidirectional"))
    )
    (net (code "93") (name "unconnected-(SODIMM-15{slash}GPIO4-Pad15)") (class "Default")
      (node (ref "SODIMM") (pin "15") (pinfunction "15/GPIO4_15") (pintype "bidirectional"))
    )
    (net (code "94") (name "unconnected-(SODIMM-16{slash}NC-Pad16)") (class "Default")
      (node (ref "SODIMM") (pin "16") (pinfunction "16/NC_16") (pintype "bidirectional"))
    )
    (net (code "95") (name "unconnected-(SODIMM-17{slash}GPIO5-Pad17)") (class "Default")
      (node (ref "SODIMM") (pin "17") (pinfunction "17/GPIO5_17") (pintype "bidirectional"))
    )
    (net (code "96") (name "unconnected-(SODIMM-18{slash}NC-Pad18)") (class "Default")
      (node (ref "SODIMM") (pin "18") (pinfunction "18/NC_18") (pintype "bidirectional"))
    )
    (net (code "97") (name "unconnected-(SODIMM-21{slash}GPIO6-Pad21)") (class "Default")
      (node (ref "SODIMM") (pin "21") (pinfunction "21/GPIO6_21") (pintype "bidirectional"))
    )
    (net (code "98") (name "unconnected-(SODIMM-22{slash}NC-Pad22)") (class "Default")
      (node (ref "SODIMM") (pin "22") (pinfunction "22/NC_22") (pintype "bidirectional"))
    )
    (net (code "99") (name "unconnected-(SODIMM-23{slash}GPIO7-Pad23)") (class "Default")
      (node (ref "SODIMM") (pin "23") (pinfunction "23/GPIO7_23") (pintype "bidirectional"))
    )
    (net (code "100") (name "unconnected-(SODIMM-24{slash}NC-Pad24)") (class "Default")
      (node (ref "SODIMM") (pin "24") (pinfunction "24/NC_24") (pintype "bidirectional"))
    )
    (net (code "101") (name "unconnected-(SODIMM-27{slash}GPIO8-Pad27)") (class "Default")
      (node (ref "SODIMM") (pin "27") (pinfunction "27/GPIO8_27") (pintype "bidirectional"))
    )
    (net (code "102") (name "unconnected-(SODIMM-29{slash}GPIO9-Pad29)") (class "Default")
      (node (ref "SODIMM") (pin "29") (pinfunction "29/GPIO9_29") (pintype "bidirectional"))
    )
    (net (code "103") (name "unconnected-(SODIMM-33{slash}GPIO10-Pad33)") (class "Default")
      (node (ref "SODIMM") (pin "33") (pinfunction "33/GPIO10_33") (pintype "bidirectional"))
    )
    (net (code "104") (name "unconnected-(SODIMM-35{slash}GPIO11-Pad35)") (class "Default")
      (node (ref "SODIMM") (pin "35") (pinfunction "35/GPIO11_35") (pintype "bidirectional"))
    )
    (net (code "105") (name "unconnected-(SODIMM-45{slash}GPIO12-Pad45)") (class "Default")
      (node (ref "SODIMM") (pin "45") (pinfunction "45/GPIO12_45") (pintype "bidirectional"))
    )
    (net (code "106") (name "unconnected-(SODIMM-47{slash}GPIO13-Pad47)") (class "Default")
      (node (ref "SODIMM") (pin "47") (pinfunction "47/GPIO13_47") (pintype "bidirectional"))
    )
    (net (code "107") (name "unconnected-(SODIMM-52{slash}GPIO34-Pad52)") (class "Default")
      (node (ref "SODIMM") (pin "52") (pinfunction "52/GPIO34_52") (pintype "bidirectional"))
    )
    (net (code "108") (name "unconnected-(SODIMM-54{slash}GPIO35-Pad54)") (class "Default")
      (node (ref "SODIMM") (pin "54") (pinfunction "54/GPIO35_54") (pintype "bidirectional"))
    )
    (net (code "109") (name "unconnected-(SODIMM-57{slash}GPIO16-Pad57)") (class "Default")
      (node (ref "SODIMM") (pin "57") (pinfunction "57/GPIO16_57") (pintype "bidirectional"))
    )
    (net (code "110") (name "unconnected-(SODIMM-58{slash}GPIO36-Pad58)") (class "Default")
      (node (ref "SODIMM") (pin "58") (pinfunction "58/GPIO36_58") (pintype "bidirectional"))
    )
    (net (code "111") (name "unconnected-(SODIMM-59{slash}GPIO17-Pad59)") (class "Default")
      (node (ref "SODIMM") (pin "59") (pinfunction "59/GPIO17_59") (pintype "bidirectional"))
    )
    (net (code "112") (name "unconnected-(SODIMM-60{slash}GPIO37-Pad60)") (class "Default")
      (node (ref "SODIMM") (pin "60") (pinfunction "60/GPIO37_60") (pintype "bidirectional"))
    )
    (net (code "113") (name "unconnected-(SODIMM-64{slash}GPIO38-Pad64)") (class "Default")
      (node (ref "SODIMM") (pin "64") (pinfunction "64/GPIO38_64") (pintype "bidirectional"))
    )
    (net (code "114") (name "unconnected-(SODIMM-66{slash}GPIO39-Pad66)") (class "Default")
      (node (ref "SODIMM") (pin "66") (pinfunction "66/GPIO39_66") (pintype "bidirectional"))
    )
    (net (code "115") (name "unconnected-(SODIMM-70{slash}GPIO40-Pad70)") (class "Default")
      (node (ref "SODIMM") (pin "70") (pinfunction "70/GPIO40_70") (pintype "bidirectional"))
    )
    (net (code "116") (name "unconnected-(SODIMM-72{slash}GPIO41-Pad72)") (class "Default")
      (node (ref "SODIMM") (pin "72") (pinfunction "72/GPIO41_72") (pintype "bidirectional"))
    )
    (net (code "117") (name "unconnected-(SODIMM-75{slash}GPIO22-Pad75)") (class "Default")
      (node (ref "SODIMM") (pin "75") (pinfunction "75/GPIO22_75") (pintype "bidirectional"))
    )
    (net (code "118") (name "unconnected-(SODIMM-76{slash}GPIO42-Pad76)") (class "Default")
      (node (ref "SODIMM") (pin "76") (pinfunction "76/GPIO42_76") (pintype "bidirectional"))
    )
    (net (code "119") (name "unconnected-(SODIMM-77{slash}GPIO23-Pad77)") (class "Default")
      (node (ref "SODIMM") (pin "77") (pinfunction "77/GPIO23_77") (pintype "bidirectional"))
    )
    (net (code "120") (name "unconnected-(SODIMM-78{slash}GPIO43-Pad78)") (class "Default")
      (node (ref "SODIMM") (pin "78") (pinfunction "78/GPIO43_78") (pintype "bidirectional"))
    )
    (net (code "121") (name "unconnected-(SODIMM-81{slash}GPIO24-Pad81)") (class "Default")
      (node (ref "SODIMM") (pin "81") (pinfunction "81/GPIO24_81") (pintype "bidirectional"))
    )
    (net (code "122") (name "unconnected-(SODIMM-82{slash}GPIO44-Pad82)") (class "Default")
      (node (ref "SODIMM") (pin "82") (pinfunction "82/GPIO44_82") (pintype "bidirectional"))
    )
    (net (code "123") (name "unconnected-(SODIMM-83{slash}GPIO25-Pad83)") (class "Default")
      (node (ref "SODIMM") (pin "83") (pinfunction "83/GPIO25_83") (pintype "bidirectional"))
    )
    (net (code "124") (name "unconnected-(SODIMM-84{slash}GPIO45-Pad84)") (class "Default")
      (node (ref "SODIMM") (pin "84") (pinfunction "84/GPIO45_84") (pintype "bidirectional"))
    )
    (net (code "125") (name "unconnected-(SODIMM-87{slash}GPIO26-Pad87)") (class "Default")
      (node (ref "SODIMM") (pin "87") (pinfunction "87/GPIO26_87") (pintype "bidirectional"))
    )
    (net (code "126") (name "unconnected-(SODIMM-89{slash}GPIO27-Pad89)") (class "Default")
      (node (ref "SODIMM") (pin "89") (pinfunction "89/GPIO27_89") (pintype "bidirectional"))
    )
    (net (code "127") (name "unconnected-(SODIMM-90{slash}GPIO47_1V8-Pad90)") (class "Default")
      (node (ref "SODIMM") (pin "90") (pinfunction "90/GPIO47_1V8_90") (pintype "bidirectional"))
    )
    (net (code "128") (name "unconnected-(SODIMM-93{slash}DSI0_DN1*-Pad93)") (class "Default")
      (node (ref "SODIMM") (pin "93") (pinfunction "93/DSI0_DN1*_93") (pintype "bidirectional"))
    )
    (net (code "129") (name "unconnected-(SODIMM-94{slash}DSI1_DP0*-Pad94)") (class "Default")
      (node (ref "SODIMM") (pin "94") (pinfunction "94/DSI1_DP0*_94") (pintype "bidirectional"))
    )
    (net (code "130") (name "unconnected-(SODIMM-95{slash}DSI0_DP1*-Pad95)") (class "Default")
      (node (ref "SODIMM") (pin "95") (pinfunction "95/DSI0_DP1*_95") (pintype "bidirectional"))
    )
    (net (code "131") (name "unconnected-(SODIMM-96{slash}DSI1_DN0*-Pad96)") (class "Default")
      (node (ref "SODIMM") (pin "96") (pinfunction "96/DSI1_DN0*_96") (pintype "bidirectional"))
    )
    (net (code "132") (name "unconnected-(SODIMM-99{slash}DSI0_DN0*-Pad99)") (class "Default")
      (node (ref "SODIMM") (pin "99") (pinfunction "99/DSI0_DN0*_99") (pintype "bidirectional"))
    )
    (net (code "133") (name "unconnected-(SODIMM-100{slash}DSI1CP*-Pad100)") (class "Default")
      (node (ref "SODIMM") (pin "100") (pinfunction "100/DSI1CP*_100") (pintype "bidirectional"))
    )
    (net (code "134") (name "unconnected-(SODIMM-101{slash}DSI0_DP0*-Pad101)") (class "Default")
      (node (ref "SODIMM") (pin "101") (pinfunction "101/DSI0_DP0*_101") (pintype "bidirectional"))
    )
    (net (code "135") (name "unconnected-(SODIMM-102{slash}DSI1CN*-Pad102)") (class "Default")
      (node (ref "SODIMM") (pin "102") (pinfunction "102/DSI1CN*_102") (pintype "bidirectional"))
    )
    (net (code "136") (name "unconnected-(SODIMM-105{slash}DSI0_CN*-Pad105)") (class "Default")
      (node (ref "SODIMM") (pin "105") (pinfunction "105/DSI0_CN*_105") (pintype "bidirectional"))
    )
    (net (code "137") (name "unconnected-(SODIMM-106{slash}DSI1_DP3*-Pad106)") (class "Default")
      (node (ref "SODIMM") (pin "106") (pinfunction "106/DSI1_DP3*_106") (pintype "bidirectional"))
    )
    (net (code "138") (name "unconnected-(SODIMM-107{slash}DSI0_CP*-Pad107)") (class "Default")
      (node (ref "SODIMM") (pin "107") (pinfunction "107/DSI0_CP*_107") (pintype "bidirectional"))
    )
    (net (code "139") (name "unconnected-(SODIMM-108{slash}DSI1_DN3*-Pad108)") (class "Default")
      (node (ref "SODIMM") (pin "108") (pinfunction "108/DSI1_DN3*_108") (pintype "bidirectional"))
    )
    (net (code "140") (name "unconnected-(SODIMM-112{slash}DSI1_DP2*-Pad112)") (class "Default")
      (node (ref "SODIMM") (pin "112") (pinfunction "112/DSI1_DP2*_112") (pintype "bidirectional"))
    )
    (net (code "141") (name "unconnected-(SODIMM-114{slash}DSI1_DN2*-Pad114)") (class "Default")
      (node (ref "SODIMM") (pin "114") (pinfunction "114/DSI1_DN2*_114") (pintype "bidirectional"))
    )
    (net (code "142") (name "unconnected-(SODIMM-118{slash}DSI1_DP1*-Pad118)") (class "Default")
      (node (ref "SODIMM") (pin "118") (pinfunction "118/DSI1_DP1*_118") (pintype "bidirectional"))
    )
    (net (code "143") (name "unconnected-(SODIMM-120{slash}DSI1_DN1*-Pad120)") (class "Default")
      (node (ref "SODIMM") (pin "120") (pinfunction "120/DSI1_DN1*_120") (pintype "bidirectional"))
    )
    (net (code "144") (name "unconnected-(SODIMM-124{slash}NC-Pad124)") (class "Default")
      (node (ref "SODIMM") (pin "124") (pinfunction "124/NC_124") (pintype "bidirectional"))
    )
    (net (code "145") (name "unconnected-(SODIMM-126{slash}NC-Pad126)") (class "Default")
      (node (ref "SODIMM") (pin "126") (pinfunction "126/NC_126") (pintype "bidirectional"))
    )
    (net (code "146") (name "unconnected-(SODIMM-128{slash}NC-Pad128)") (class "Default")
      (node (ref "SODIMM") (pin "128") (pinfunction "128/NC_128") (pintype "bidirectional"))
    )
    (net (code "147") (name "unconnected-(SODIMM-130{slash}NC-Pad130)") (class "Default")
      (node (ref "SODIMM") (pin "130") (pinfunction "130/NC_130") (pintype "bidirectional"))
    )
    (net (code "148") (name "unconnected-(SODIMM-132{slash}NC-Pad132)") (class "Default")
      (node (ref "SODIMM") (pin "132") (pinfunction "132/NC_132") (pintype "bidirectional"))
    )
    (net (code "149") (name "unconnected-(SODIMM-135{slash}CAM1_DP3*-Pad135)") (class "Default")
      (node (ref "SODIMM") (pin "135") (pinfunction "135/CAM1_DP3*_135") (pintype "bidirectional"))
    )
    (net (code "150") (name "unconnected-(SODIMM-136{slash}CAM0_DP0*-Pad136)") (class "Default")
      (node (ref "SODIMM") (pin "136") (pinfunction "136/CAM0_DP0*_136") (pintype "bidirectional"))
    )
    (net (code "151") (name "unconnected-(SODIMM-137{slash}CAM1_DN3*-Pad137)") (class "Default")
      (node (ref "SODIMM") (pin "137") (pinfunction "137/CAM1_DN3*_137") (pintype "bidirectional"))
    )
    (net (code "152") (name "unconnected-(SODIMM-138{slash}CAM0_DN0*-Pad138)") (class "Default")
      (node (ref "SODIMM") (pin "138") (pinfunction "138/CAM0_DN0*_138") (pintype "bidirectional"))
    )
    (net (code "153") (name "unconnected-(SODIMM-141{slash}CAM1_DP2*-Pad141)") (class "Default")
      (node (ref "SODIMM") (pin "141") (pinfunction "141/CAM1_DP2*_141") (pintype "bidirectional"))
    )
    (net (code "154") (name "unconnected-(SODIMM-142{slash}CAM0_CP*-Pad142)") (class "Default")
      (node (ref "SODIMM") (pin "142") (pinfunction "142/CAM0_CP*_142") (pintype "bidirectional"))
    )
    (net (code "155") (name "unconnected-(SODIMM-143{slash}CAM1_DN2*-Pad143)") (class "Default")
      (node (ref "SODIMM") (pin "143") (pinfunction "143/CAM1_DN2*_143") (pintype "bidirectional"))
    )
    (net (code "156") (name "unconnected-(SODIMM-144{slash}CAM0_CN*-Pad144)") (class "Default")
      (node (ref "SODIMM") (pin "144") (pinfunction "144/CAM0_CN*_144") (pintype "bidirectional"))
    )
    (net (code "157") (name "unconnected-(SODIMM-147{slash}CAM1_CP*-Pad147)") (class "Default")
      (node (ref "SODIMM") (pin "147") (pinfunction "147/CAM1_CP*_147") (pintype "bidirectional"))
    )
    (net (code "158") (name "unconnected-(SODIMM-148{slash}CAM0_DP1*-Pad148)") (class "Default")
      (node (ref "SODIMM") (pin "148") (pinfunction "148/CAM0_DP1*_148") (pintype "bidirectional"))
    )
    (net (code "159") (name "unconnected-(SODIMM-149{slash}CAM1_CN*-Pad149)") (class "Default")
      (node (ref "SODIMM") (pin "149") (pinfunction "149/CAM1_CN*_149") (pintype "bidirectional"))
    )
    (net (code "160") (name "unconnected-(SODIMM-150{slash}CAM0_DN1*-Pad150)") (class "Default")
      (node (ref "SODIMM") (pin "150") (pinfunction "150/CAM0_DN1*_150") (pintype "bidirectional"))
    )
    (net (code "161") (name "unconnected-(SODIMM-153{slash}CAM1_DP1*-Pad153)") (class "Default")
      (node (ref "SODIMM") (pin "153") (pinfunction "153/CAM1_DP1*_153") (pintype "bidirectional"))
    )
    (net (code "162") (name "unconnected-(SODIMM-154{slash}NC-Pad154)") (class "Default")
      (node (ref "SODIMM") (pin "154") (pinfunction "154/NC_154") (pintype "bidirectional"))
    )
    (net (code "163") (name "unconnected-(SODIMM-155{slash}CAM1_DN1*-Pad155)") (class "Default")
      (node (ref "SODIMM") (pin "155") (pinfunction "155/CAM1_DN1*_155") (pintype "bidirectional"))
    )
    (net (code "164") (name "unconnected-(SODIMM-156{slash}NC-Pad156)") (class "Default")
      (node (ref "SODIMM") (pin "156") (pinfunction "156/NC_156") (pintype "bidirectional"))
    )
    (net (code "165") (name "unconnected-(SODIMM-158{slash}NC-Pad158)") (class "Default")
      (node (ref "SODIMM") (pin "158") (pinfunction "158/NC_158") (pintype "bidirectional"))
    )
    (net (code "166") (name "unconnected-(SODIMM-159{slash}CAM1_DP0*-Pad159)") (class "Default")
      (node (ref "SODIMM") (pin "159") (pinfunction "159/CAM1_DP0*_159") (pintype "bidirectional"))
    )
    (net (code "167") (name "unconnected-(SODIMM-160{slash}NC-Pad160)") (class "Default")
      (node (ref "SODIMM") (pin "160") (pinfunction "160/NC_160") (pintype "bidirectional"))
    )
    (net (code "168") (name "unconnected-(SODIMM-161{slash}CAM1_DN0*-Pad161)") (class "Default")
      (node (ref "SODIMM") (pin "161") (pinfunction "161/CAM1_DN0*_161") (pintype "bidirectional"))
    )
    (net (code "169") (name "unconnected-(SODIMM-162{slash}NC-Pad162)") (class "Default")
      (node (ref "SODIMM") (pin "162") (pinfunction "162/NC_162") (pintype "bidirectional"))
    )
    (net (code "170") (name "unconnected-(SODIMM-166{slash}TVDAC-Pad166)") (class "Default")
      (node (ref "SODIMM") (pin "166") (pinfunction "166/TVDAC_166") (pintype "bidirectional"))
    )
    (net (code "171") (name "unconnected-(SODIMM-172{slash}VC_TRST_N-Pad172)") (class "Default")
      (node (ref "SODIMM") (pin "172") (pinfunction "172/VC_TRST_N_172") (pintype "bidirectional"))
    )
    (net (code "172") (name "unconnected-(SODIMM-174{slash}VC_TDI-Pad174)") (class "Default")
      (node (ref "SODIMM") (pin "174") (pinfunction "174/VC_TDI_174") (pintype "bidirectional"))
    )
    (net (code "173") (name "unconnected-(SODIMM-176{slash}VC_TMS-Pad176)") (class "Default")
      (node (ref "SODIMM") (pin "176") (pinfunction "176/VC_TMS_176") (pintype "bidirectional"))
    )
    (net (code "174") (name "unconnected-(SODIMM-177{slash}RUN-Pad177)") (class "Default")
      (node (ref "SODIMM") (pin "177") (pinfunction "177/RUN_177") (pintype "bidirectional"))
    )
    (net (code "175") (name "unconnected-(SODIMM-178{slash}VC_TDO-Pad178)") (class "Default")
      (node (ref "SODIMM") (pin "178") (pinfunction "178/VC_TDO_178") (pintype "bidirectional"))
    )
    (net (code "176") (name "unconnected-(SODIMM-179{slash}VDD_CORE-Pad179)") (class "Default")
      (node (ref "SODIMM") (pin "179") (pinfunction "179/VDD_CORE_179") (pintype "bidirectional"))
    )
    (net (code "177") (name "unconnected-(SODIMM-180{slash}VC_TCK-Pad180)") (class "Default")
      (node (ref "SODIMM") (pin "180") (pinfunction "180/VC_TCK_180") (pintype "bidirectional"))
    )
    (net (code "178") (name "unconnected-(TP_RTC_32K1-PadTP)") (class "Default")
      (node (ref "TP_RTC_32K1") (pin "TP") (pinfunction "TP_TP") (pintype "input"))
    )
    (net (code "179") (name "unconnected-(TP_RTC_INT1-PadTP)") (class "Default")
      (node (ref "TP_RTC_INT1") (pin "TP") (pinfunction "TP_TP") (pintype "input"))
    )
    (net (code "180") (name "unconnected-(U4-DIO3-Pad3P)") (class "Default")
      (node (ref "U4") (pin "3P") (pinfunction "DIO3_3P") (pintype "bidirectional"))
    )
    (net (code "181") (name "unconnected-(U4-DIO4-Pad4P)") (class "Default")
      (node (ref "U4") (pin "4P") (pinfunction "DIO4_4P") (pintype "bidirectional"))
    )
    (net (code "182") (name "unconnected-(U4-DIO5-Pad15P)") (class "Default")
      (node (ref "U4") (pin "15P") (pinfunction "DIO5_15P") (pintype "bidirectional"))
    )
  )
)
